# Top_Level.net
KiCad netlist of a schematic drawn in Altium Designer
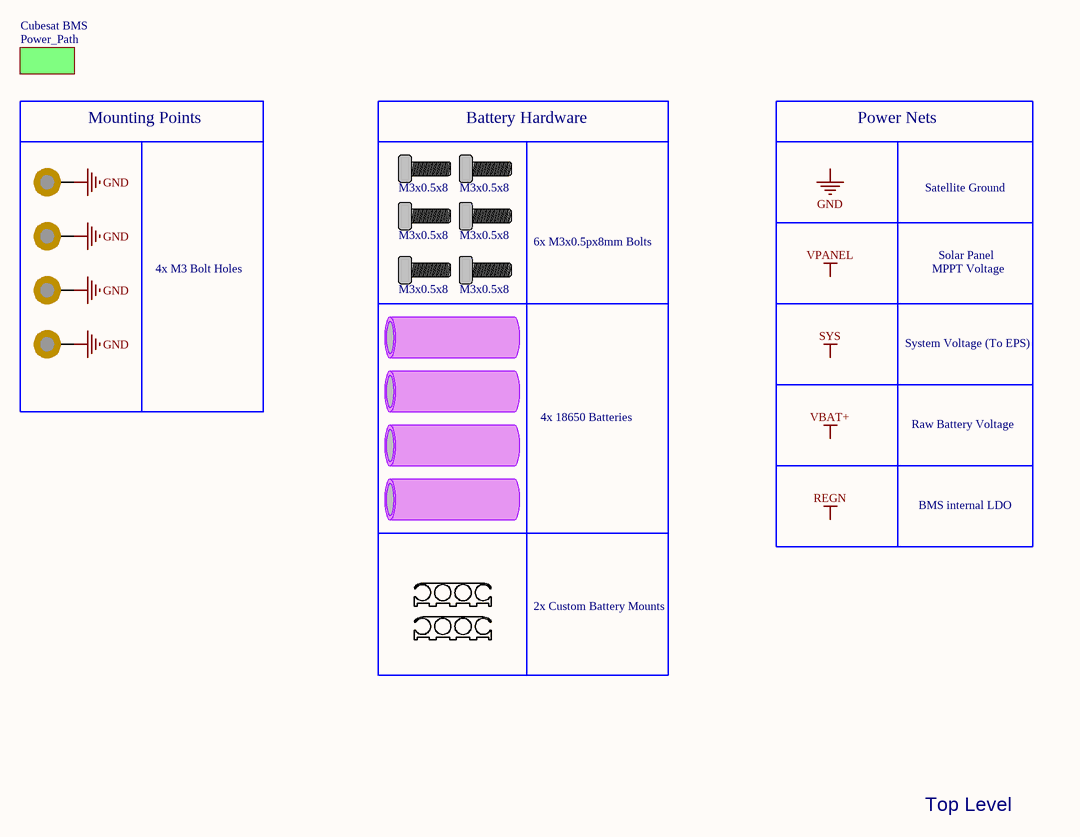
[diagram p0: Top_Level.SchDoc]

(export (version "E")
  (design (tool "Eeschema 10.0.6"))
  (components
    (comp (ref "BAT1")
      (value "INR18650-35E")
      (description "Samsung 3500mAh 18650 Li-Ion battery")
      (fields (field (name "DISTRIBUTOR PART NUMBER") "SB2632"))
      (libsource (lib "Ahristi_Library") (part "INR18650-35E"))
    )
    (comp (ref "BAT2")
      (value "INR18650-35E")
      (description "Samsung 3500mAh 18650 Li-Ion battery")
      (fields (field (name "DISTRIBUTOR PART NUMBER") "SB2632"))
      (libsource (lib "Ahristi_Library") (part "INR18650-35E"))
    )
    (comp (ref "BAT3")
      (value "INR18650-35E")
      (description "Samsung 3500mAh 18650 Li-Ion battery")
      (fields (field (name "DISTRIBUTOR PART NUMBER") "SB2632"))
      (libsource (lib "Ahristi_Library") (part "INR18650-35E"))
    )
    (comp (ref "BAT4")
      (value "INR18650-35E")
      (description "Samsung 3500mAh 18650 Li-Ion battery")
      (fields (field (name "DISTRIBUTOR PART NUMBER") "SB2632"))
      (libsource (lib "Ahristi_Library") (part "INR18650-35E"))
    )
    (comp (ref "MECH1")
      (value "M3 Mounting Hole")
      (footprint "M3 Mounting Hole")
      (libsource (lib "Ahristi_Library") (part "M3 Mounting Hole"))
    )
    (comp (ref "MECH2")
      (value "M3 Mounting Hole")
      (footprint "M3 Mounting Hole")
      (libsource (lib "Ahristi_Library") (part "M3 Mounting Hole"))
    )
    (comp (ref "MECH3")
      (value "M3 Mounting Hole")
      (footprint "M3 Mounting Hole")
      (libsource (lib "Ahristi_Library") (part "M3 Mounting Hole"))
    )
    (comp (ref "MECH4")
      (value "M3 Mounting Hole")
      (footprint "M3 Mounting Hole")
      (libsource (lib "Ahristi_Library") (part "M3 Mounting Hole"))
    )
    (comp (ref "MECH5")
      (value "M3x0.5x8")
      (footprint "M3 x 0.50p x 8mm Bolt")
      (fields (field (name "PART NUMBER") "M3 x 0.50p x 8mm"))
      (libsource (lib "Ahristi_Library") (part "M3x0.5px8mm Bolt"))
    )
    (comp (ref "MECH6")
      (value "M3x0.5x8")
      (footprint "M3 x 0.50p x 8mm Bolt")
      (fields (field (name "PART NUMBER") "M3 x 0.50p x 8mm"))
      (libsource (lib "Ahristi_Library") (part "M3x0.5px8mm Bolt"))
    )
    (comp (ref "MECH7")
      (value "M3x0.5x8")
      (footprint "M3 x 0.50p x 8mm Bolt")
      (fields (field (name "PART NUMBER") "M3 x 0.50p x 8mm"))
      (libsource (lib "Ahristi_Library") (part "M3x0.5px8mm Bolt"))
    )
    (comp (ref "MECH8")
      (value "M3x0.5x8")
      (footprint "M3 x 0.50p x 8mm Bolt")
      (fields (field (name "PART NUMBER") "M3 x 0.50p x 8mm"))
      (libsource (lib "Ahristi_Library") (part "M3x0.5px8mm Bolt"))
    )
    (comp (ref "MECH9")
      (value "M3x0.5x8")
      (footprint "M3 x 0.50p x 8mm Bolt")
      (fields (field (name "PART NUMBER") "M3 x 0.50p x 8mm"))
      (libsource (lib "Ahristi_Library") (part "M3x0.5px8mm Bolt"))
    )
    (comp (ref "MECH10")
      (value "M3x0.5x8")
      (footprint "M3 x 0.50p x 8mm Bolt")
      (fields (field (name "PART NUMBER") "M3 x 0.50p x 8mm"))
      (libsource (lib "Ahristi_Library") (part "M3x0.5px8mm Bolt"))
    )
  )
  (nets
    (net (code "1") (name "GND") (class "Default")
      (node (ref "MECH1") (pin "1") (pinfunction "1_1") (pintype "passive"))
      (node (ref "MECH2") (pin "1") (pinfunction "1_1") (pintype "passive"))
      (node (ref "MECH3") (pin "1") (pinfunction "1_1") (pintype "passive"))
      (node (ref "MECH4") (pin "1") (pinfunction "1_1") (pintype "passive"))
    )
  )
)
